# CON_PCPPORT_26WBOXHDRRAM.net
KiCad netlist of a schematic drawn in Altium Designer
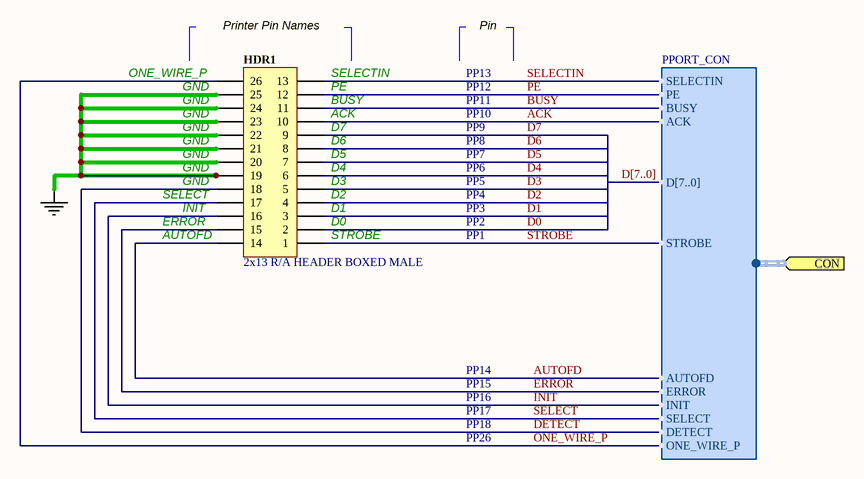
[diagram p0: CON_PCPPORT_26WBOXHDRRAM.SchDoc]

(export (version "E")
  (design (tool "Eeschema 10.0.6"))
  (components
    (comp (ref "HDR1")
      (value "2x13 R/A HEADER BOXED MALE")
      (footprint "HDR2X13_RA_CENTRONICS")
      (description "Header IDC, 2 x 13 Pin Right-Angle 2.54mm Pitch (Boxed-Male)")
      (libsource (lib "altium-import") (part "root_2_CON-IDC-2x13-M-RA_"))
    )
  )
  (nets
    (net (code "2") (name "/ACK") (class "Default")
      (node (ref "HDR1") (pin "10") (pinfunction "10_10") (pintype "passive"))
    )
    (net (code "3") (name "/AUTOFD") (class "Default")
      (node (ref "HDR1") (pin "14") (pinfunction "14_14") (pintype "passive"))
    )
    (net (code "4") (name "/BUSY") (class "Default")
      (node (ref "HDR1") (pin "11") (pinfunction "11_11") (pintype "passive"))
    )
    (net (code "6") (name "/D0") (class "Default")
      (node (ref "HDR1") (pin "2") (pinfunction "2_2") (pintype "passive"))
    )
    (net (code "7") (name "/D1") (class "Default")
      (node (ref "HDR1") (pin "3") (pinfunction "3_3") (pintype "passive"))
    )
    (net (code "8") (name "/D2") (class "Default")
      (node (ref "HDR1") (pin "4") (pinfunction "4_4") (pintype "passive"))
    )
    (net (code "9") (name "/D3") (class "Default")
      (node (ref "HDR1") (pin "5") (pinfunction "5_5") (pintype "passive"))
    )
    (net (code "10") (name "/D4") (class "Default")
      (node (ref "HDR1") (pin "6") (pinfunction "6_6") (pintype "passive"))
    )
    (net (code "11") (name "/D5") (class "Default")
      (node (ref "HDR1") (pin "7") (pinfunction "7_7") (pintype "passive"))
    )
    (net (code "12") (name "/D6") (class "Default")
      (node (ref "HDR1") (pin "8") (pinfunction "8_8") (pintype "passive"))
    )
    (net (code "13") (name "/D7") (class "Default")
      (node (ref "HDR1") (pin "9") (pinfunction "9_9") (pintype "passive"))
    )
    (net (code "14") (name "/DETECT") (class "Default")
      (node (ref "HDR1") (pin "18") (pinfunction "18_18") (pintype "passive"))
    )
    (net (code "15") (name "/ERROR") (class "Default")
      (node (ref "HDR1") (pin "15") (pinfunction "15_15") (pintype "passive"))
    )
    (net (code "16") (name "/INIT") (class "Default")
      (node (ref "HDR1") (pin "16") (pinfunction "16_16") (pintype "passive"))
    )
    (net (code "17") (name "/ONE_WIRE_P") (class "Default")
      (node (ref "HDR1") (pin "26") (pinfunction "26_26") (pintype "passive"))
    )
    (net (code "18") (name "/PE") (class "Default")
      (node (ref "HDR1") (pin "12") (pinfunction "12_12") (pintype "passive"))
    )
    (net (code "19") (name "/SELECT") (class "Default")
      (node (ref "HDR1") (pin "17") (pinfunction "17_17") (pintype "passive"))
    )
    (net (code "20") (name "/SELECTIN") (class "Default")
      (node (ref "HDR1") (pin "13") (pinfunction "13_13") (pintype "passive"))
    )
    (net (code "21") (name "/STROBE") (class "Default")
      (node (ref "HDR1") (pin "1") (pinfunction "1_1") (pintype "passive"))
    )
    (net (code "23") (name "GND") (class "Default")
      (node (ref "HDR1") (pin "19") (pinfunction "19_19") (pintype "passive"))
      (node (ref "HDR1") (pin "20") (pinfunction "20_20") (pintype "passive"))
      (node (ref "HDR1") (pin "21") (pinfunction "21_21") (pintype "passive"))
      (node (ref "HDR1") (pin "22") (pinfunction "22_22") (pintype "passive"))
      (node (ref "HDR1") (pin "23") (pinfunction "23_23") (pintype "passive"))
      (node (ref "HDR1") (pin "24") (pinfunction "24_24") (pintype "passive"))
      (node (ref "HDR1") (pin "25") (pinfunction "25_25") (pintype "passive"))
    )
  )
)
